# zhangting_v0_0.net
KiCad netlist of a schematic drawn in Altium Designer
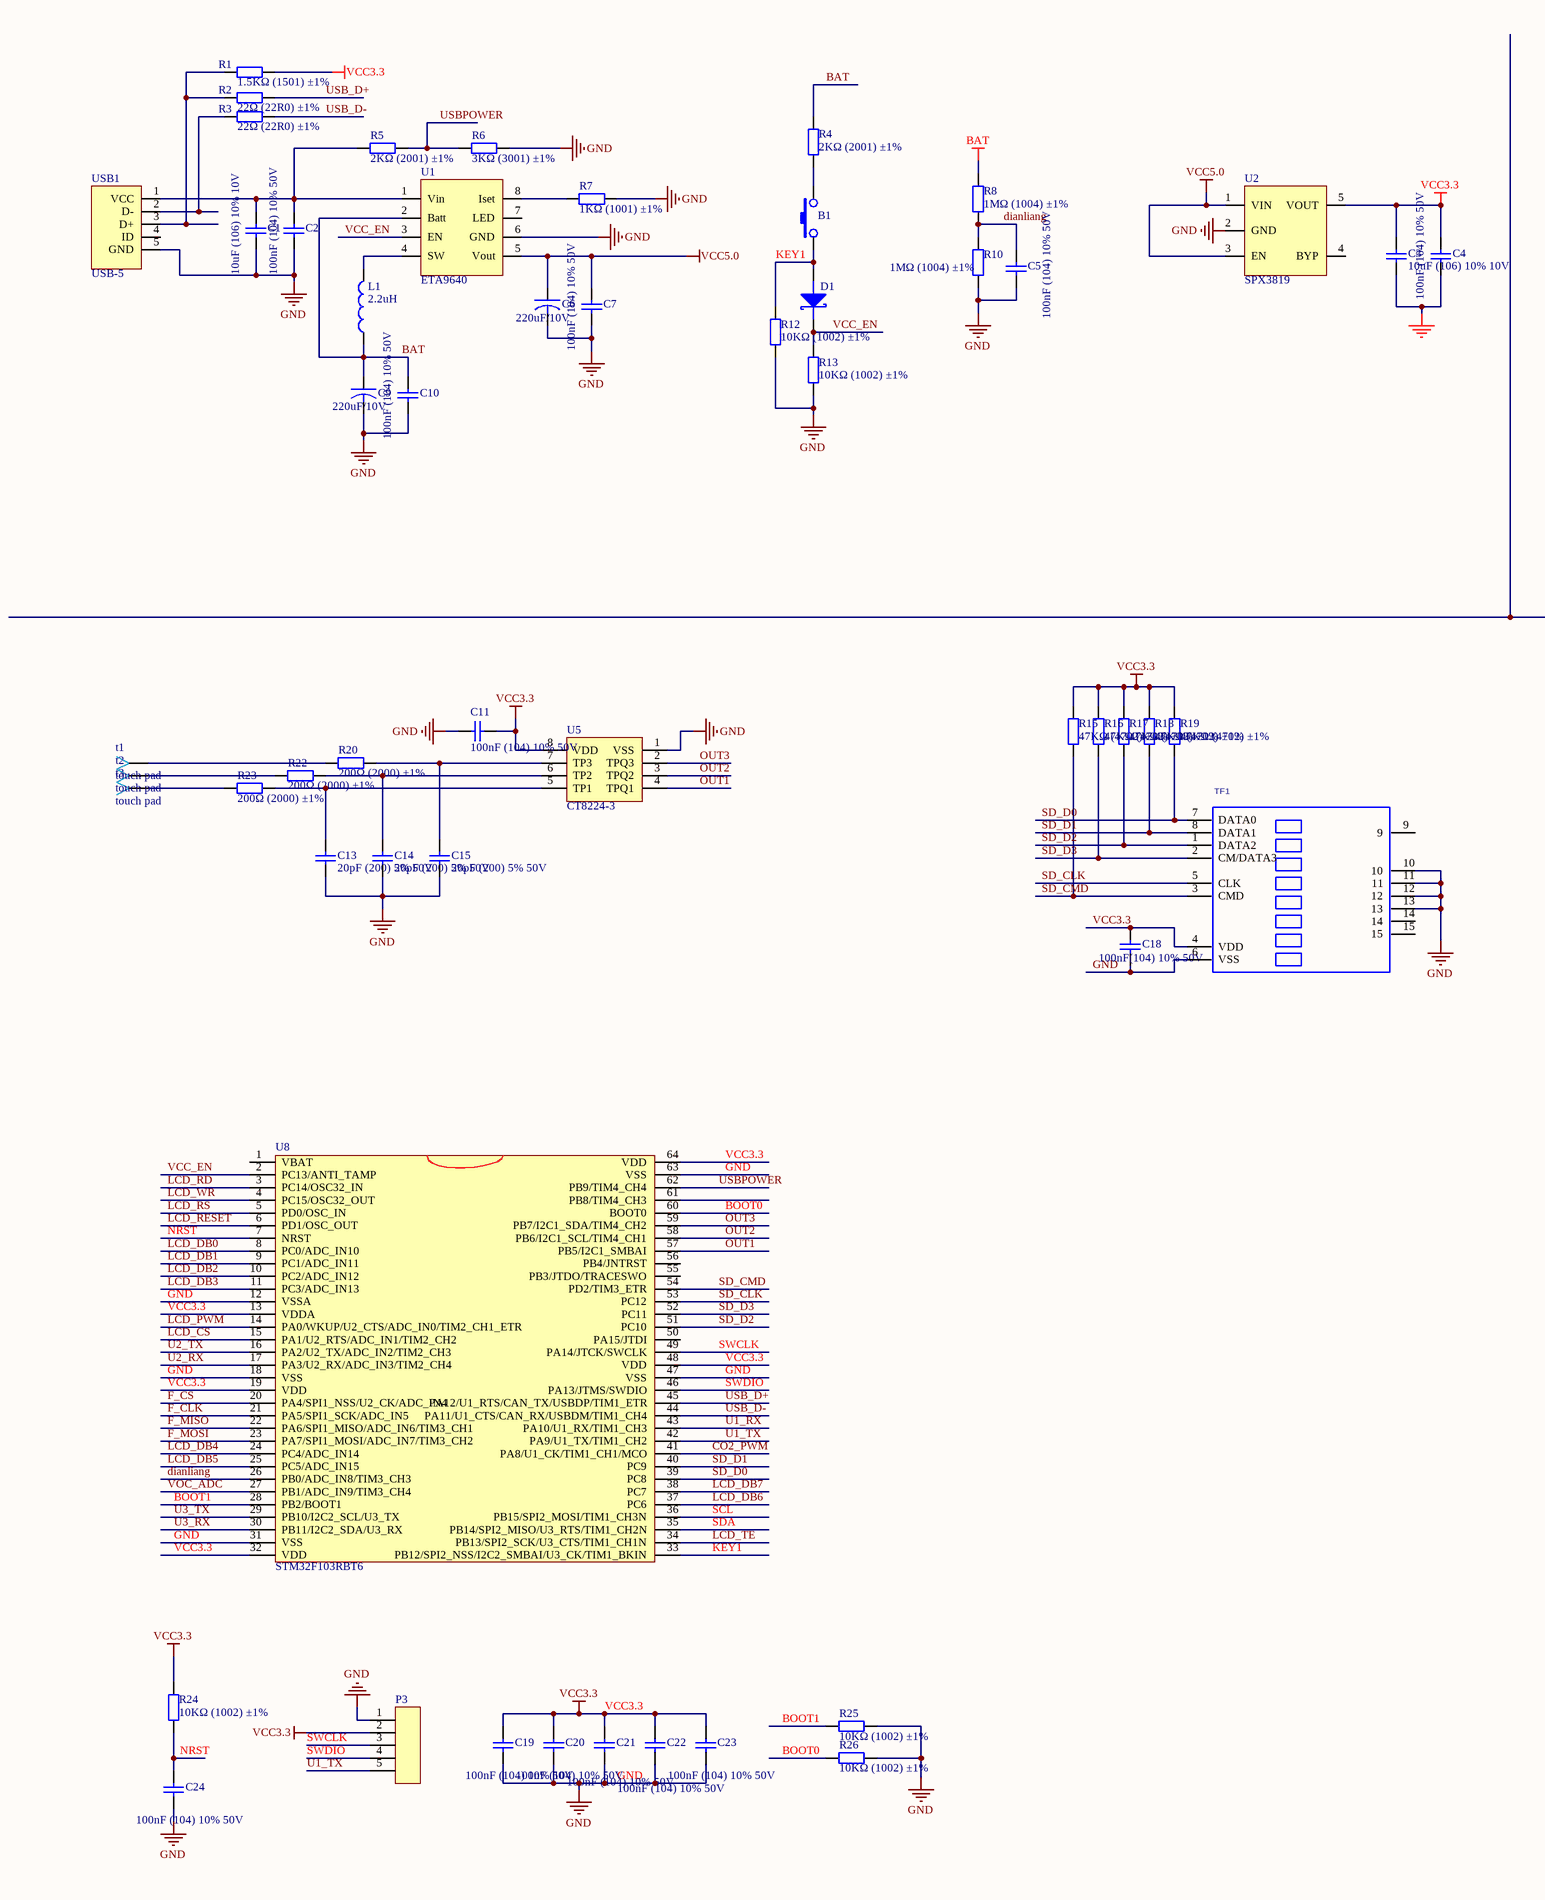
[diagram p0: zhangting v0.0.SchDoc, left]
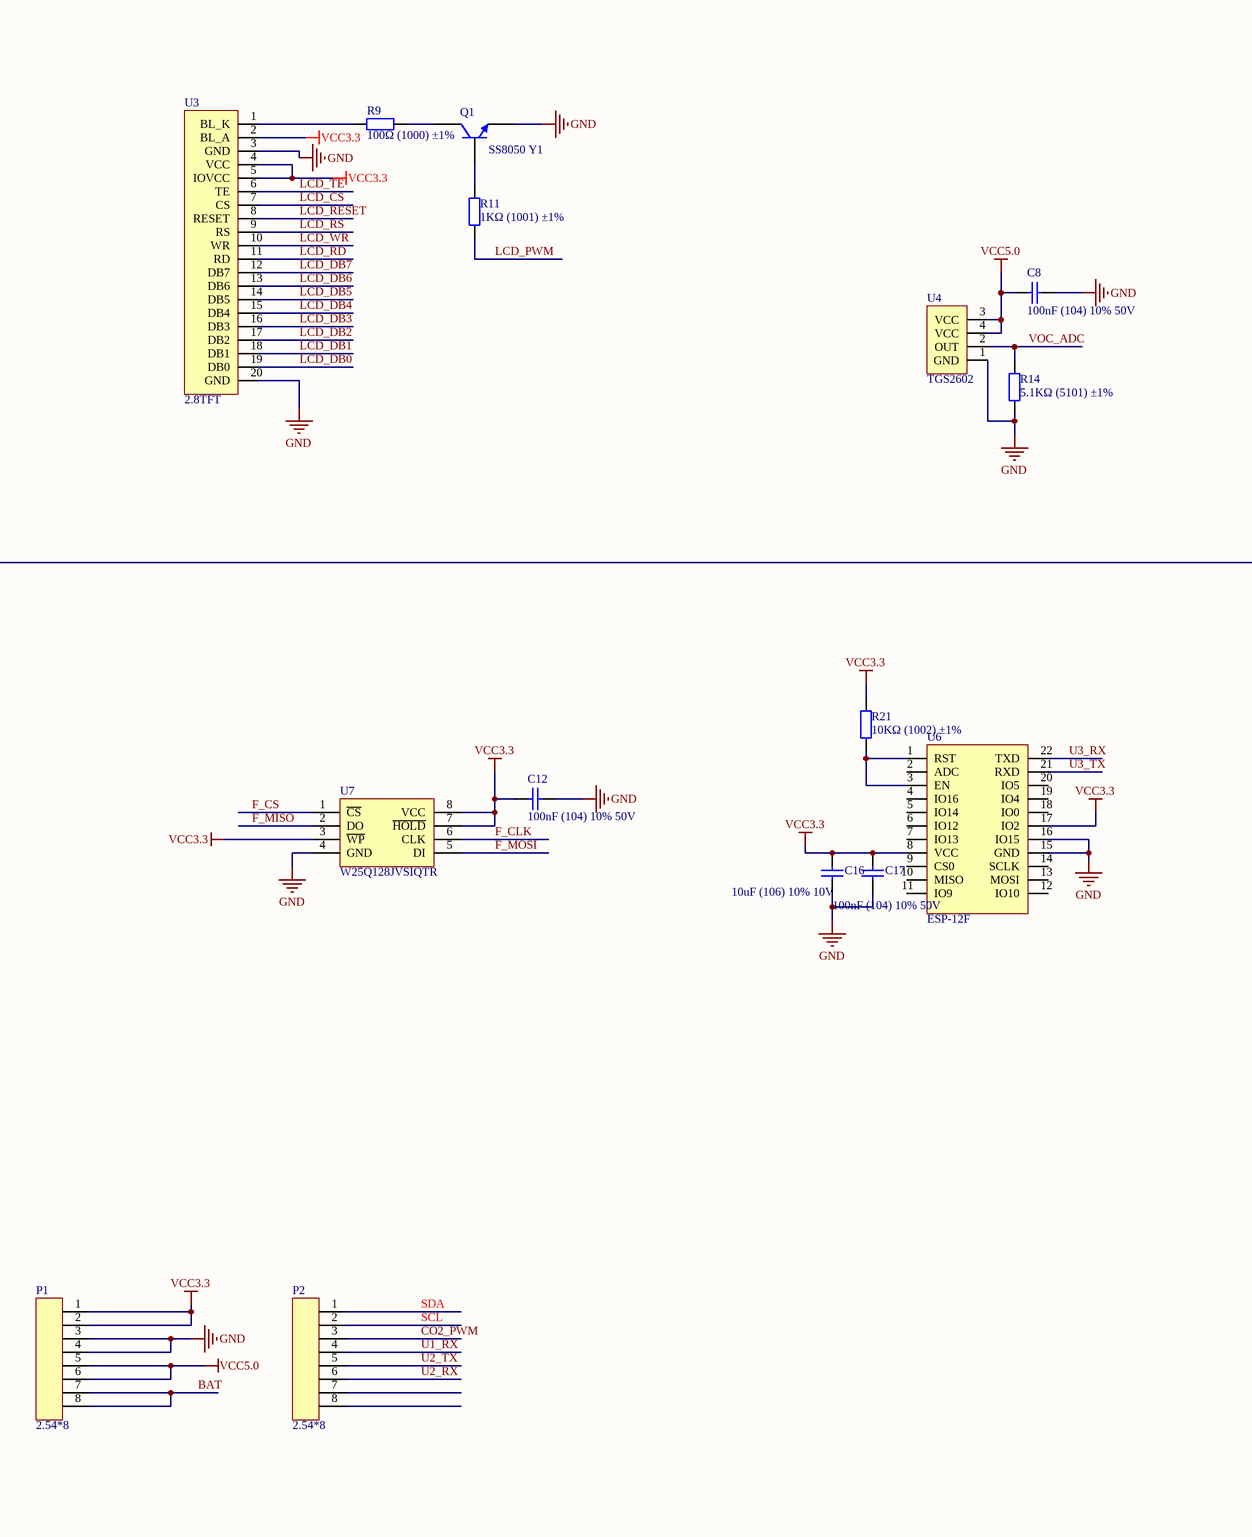
[diagram p1: zhangting v0.0.SchDoc, right]

(export (version "E")
  (design (tool "Eeschema 10.0.6"))
  (components
    (comp (ref "B1") (value "BUTTON侧贴") (footprint "BUTTON侧贴") (libsource (lib "分立器件") (part "BUTTON侧贴")))
    (comp (ref "C1")
      (value "10uF (106) 10% 10V")
      (footprint "0603_C")
      (description "贴片电容")
      (libsource (lib "Miscellaneous Devices LC") (part "0603 10uF (106) 10% 10V"))
    )
    (comp (ref "C2")
      (value "100nF (104) 10% 50V")
      (footprint "0603_C")
      (description "贴片电容")
      (libsource (lib "Miscellaneous Devices LC") (part "0603 100nF (104) 10% 50V"))
    )
    (comp (ref "C3")
      (value "10uF (106) 10% 10V")
      (footprint "0603_C")
      (description "贴片电容")
      (libsource (lib "Miscellaneous Devices LC") (part "0603 10uF (106) 10% 10V"))
    )
    (comp (ref "C4")
      (value "100nF (104) 10% 50V")
      (footprint "0603_C")
      (description "贴片电容")
      (libsource (lib "Miscellaneous Devices LC") (part "0603 100nF (104) 10% 50V"))
    )
    (comp (ref "C5")
      (value "100nF (104) 10% 50V")
      (footprint "0603_C")
      (description "贴片电容")
      (libsource (lib "Miscellaneous Devices LC") (part "0603 100nF (104) 10% 50V"))
    )
    (comp (ref "C6") (value "220uF/10V") (footprint "SMD-6.5mm") (libsource (lib "分立器件") (part "SMD-CAP")))
    (comp (ref "C7")
      (value "100nF (104) 10% 50V")
      (footprint "0603_C")
      (description "贴片电容")
      (libsource (lib "Miscellaneous Devices LC") (part "0603 100nF (104) 10% 50V"))
    )
    (comp (ref "C8")
      (value "100nF (104) 10% 50V")
      (footprint "0603_C")
      (description "贴片电容")
      (libsource (lib "Miscellaneous Devices LC") (part "0603 100nF (104) 10% 50V"))
    )
    (comp (ref "C9") (value "220uF/10V") (footprint "SMD-6.5mm") (libsource (lib "分立器件") (part "SMD-CAP")))
    (comp (ref "C10")
      (value "100nF (104) 10% 50V")
      (footprint "0603_C")
      (description "贴片电容")
      (libsource (lib "Miscellaneous Devices LC") (part "0603 100nF (104) 10% 50V"))
    )
    (comp (ref "C11")
      (value "100nF (104) 10% 50V")
      (footprint "0603_C")
      (description "贴片电容")
      (libsource (lib "Miscellaneous Devices LC") (part "0603 100nF (104) 10% 50V"))
    )
    (comp (ref "C12")
      (value "100nF (104) 10% 50V")
      (footprint "0603_C")
      (description "贴片电容")
      (libsource (lib "Miscellaneous Devices LC") (part "0603 100nF (104) 10% 50V"))
    )
    (comp (ref "C13")
      (value "20pF (200) 5% 50V")
      (footprint "0603_C")
      (description "贴片电容")
      (libsource (lib "Miscellaneous Devices LC") (part "0603 20pF (200) 5% 50V"))
    )
    (comp (ref "C14")
      (value "20pF (200) 5% 50V")
      (footprint "0603_C")
      (description "贴片电容")
      (libsource (lib "Miscellaneous Devices LC") (part "0603 20pF (200) 5% 50V"))
    )
    (comp (ref "C15")
      (value "20pF (200) 5% 50V")
      (footprint "0603_C")
      (description "贴片电容")
      (libsource (lib "Miscellaneous Devices LC") (part "0603 20pF (200) 5% 50V"))
    )
    (comp (ref "C16")
      (value "10uF (106) 10% 10V")
      (footprint "0603_C")
      (description "贴片电容")
      (libsource (lib "Miscellaneous Devices LC") (part "0603 10uF (106) 10% 10V"))
    )
    (comp (ref "C17")
      (value "100nF (104) 10% 50V")
      (footprint "0603_C")
      (description "贴片电容")
      (libsource (lib "Miscellaneous Devices LC") (part "0603 100nF (104) 10% 50V"))
    )
    (comp (ref "C18")
      (value "100nF(104) 10% 50V")
      (footprint "0805_C")
      (description "贴片电容")
      (libsource (lib "Miscellaneous Devices LC") (part "0805 100nF(104) 10% 50V"))
    )
    (comp (ref "C19")
      (value "100nF (104) 10% 50V")
      (footprint "0603_C")
      (description "贴片电容")
      (libsource (lib "Miscellaneous Devices LC") (part "0603 100nF (104) 10% 50V"))
    )
    (comp (ref "C20")
      (value "100nF (104) 10% 50V")
      (footprint "0603_C")
      (description "贴片电容")
      (libsource (lib "Miscellaneous Devices LC") (part "0603 100nF (104) 10% 50V"))
    )
    (comp (ref "C21")
      (value "100nF (104) 10% 50V")
      (footprint "0603_C")
      (description "贴片电容")
      (libsource (lib "Miscellaneous Devices LC") (part "0603 100nF (104) 10% 50V"))
    )
    (comp (ref "C22")
      (value "100nF (104) 10% 50V")
      (footprint "0603_C")
      (description "贴片电容")
      (libsource (lib "Miscellaneous Devices LC") (part "0603 100nF (104) 10% 50V"))
    )
    (comp (ref "C23")
      (value "100nF (104) 10% 50V")
      (footprint "0603_C")
      (description "贴片电容")
      (libsource (lib "Miscellaneous Devices LC") (part "0603 100nF (104) 10% 50V"))
    )
    (comp (ref "C24")
      (value "100nF (104) 10% 50V")
      (footprint "0603_C")
      (description "贴片电容")
      (libsource (lib "Miscellaneous Devices LC") (part "0603 100nF (104) 10% 50V"))
    )
    (comp (ref "D1") (value "IN4148") (footprint "DIODE(SMA)") (libsource (lib "分立器件") (part "肖特基二极管")))
    (comp (ref "L1") (value "2.2uH") (footprint "L(CD74)") (libsource (lib "分立器件") (part "L(CD74)")))
    (comp (ref "P1") (value "2.54*8") (footprint "2.54*8") (libsource (lib "接插件") (part "2.54*8")))
    (comp (ref "P2") (value "2.54*8") (footprint "2.54*8") (libsource (lib "接插件") (part "2.54*8")))
    (comp (ref "P3") (value "2.54*5") (footprint "2.54*5") (libsource (lib "接插件") (part "2.54*5")))
    (comp (ref "Q1")
      (value "SS8050 Y1")
      (footprint "SOT-23(SOT-23-3)")
      (description "三极管")
      (libsource (lib "Miscellaneous Devices LC") (part "SOT-23 SS8050 Y1"))
    )
    (comp (ref "R1")
      (value "1.5KΩ (1501) ±1%")
      (footprint "0603_R")
      (description "贴片电阻")
      (libsource (lib "Miscellaneous Devices LC") (part "0603 1.5KΩ (1501) 1%"))
    )
    (comp (ref "R2")
      (value "22Ω (22R0) ±1%")
      (footprint "0603_R")
      (description "贴片电阻")
      (libsource (lib "Miscellaneous Devices LC") (part "0603 22Ω (22R0) 1%"))
    )
    (comp (ref "R3")
      (value "22Ω (22R0) ±1%")
      (footprint "0603_R")
      (description "贴片电阻")
      (libsource (lib "Miscellaneous Devices LC") (part "0603 22Ω (22R0) 1%"))
    )
    (comp (ref "R4")
      (value "2KΩ (2001) ±1%")
      (footprint "0603_R")
      (description "贴片电阻")
      (libsource (lib "") (part "0603 2KΩ (2001) 1%_1"))
    )
    (comp (ref "R5")
      (value "2KΩ (2001) ±1%")
      (footprint "0603_R")
      (description "贴片电阻")
      (libsource (lib "Miscellaneous Devices LC") (part "0603 2KΩ (2001) 1%"))
    )
    (comp (ref "R6")
      (value "3KΩ (3001) ±1%")
      (footprint "0603_R")
      (description "贴片电阻")
      (libsource (lib "Miscellaneous Devices LC") (part "0603 3KΩ (3001) 1%"))
    )
    (comp (ref "R7")
      (value "1KΩ (1001) ±1%")
      (footprint "0603_R")
      (description "贴片电阻")
      (libsource (lib "") (part "0603 1KΩ (1001) 1%_1"))
    )
    (comp (ref "R8")
      (value "1MΩ (1004) ±1%")
      (footprint "0603_R")
      (description "贴片电阻")
      (libsource (lib "Miscellaneous Devices LC") (part "0603 1MΩ (1004) 1%"))
    )
    (comp (ref "R9")
      (value "100Ω (1000) ±1%")
      (footprint "0603_R")
      (description "贴片电阻")
      (libsource (lib "Miscellaneous Devices LC") (part "0603 100Ω (1000) 1%"))
    )
    (comp (ref "R10")
      (value "1MΩ (1004) ±1%")
      (footprint "0603_R")
      (description "贴片电阻")
      (libsource (lib "Miscellaneous Devices LC") (part "0603 1MΩ (1004) 1%"))
    )
    (comp (ref "R11")
      (value "1KΩ (1001) ±1%")
      (footprint "0603_R")
      (description "贴片电阻")
      (libsource (lib "Miscellaneous Devices LC") (part "0603 1KΩ (1001) 1%"))
    )
    (comp (ref "R12")
      (value "10KΩ (1002) ±1%")
      (footprint "0603_R")
      (description "贴片电阻")
      (libsource (lib "") (part "0603 10KΩ (1002) 1%_1"))
    )
    (comp (ref "R13")
      (value "10KΩ (1002) ±1%")
      (footprint "0603_R")
      (description "贴片电阻")
      (libsource (lib "") (part "0603 10KΩ (1002) 1%_1"))
    )
    (comp (ref "R14")
      (value "5.1KΩ (5101) ±1%")
      (footprint "0603_R")
      (description "贴片电阻")
      (libsource (lib "Miscellaneous Devices LC") (part "0603 5.1KΩ (5101) 1%"))
    )
    (comp (ref "R15")
      (value "47KΩ (4702) ±1%")
      (footprint "0603_R")
      (description "贴片电阻")
      (libsource (lib "Miscellaneous Devices LC") (part "0603 47KΩ (4702) 1%"))
    )
    (comp (ref "R16")
      (value "47KΩ (4702) ±1%")
      (footprint "0603_R")
      (description "贴片电阻")
      (libsource (lib "Miscellaneous Devices LC") (part "0603 47KΩ (4702) 1%"))
    )
    (comp (ref "R17")
      (value "47KΩ (4702) ±1%")
      (footprint "0603_R")
      (description "贴片电阻")
      (libsource (lib "Miscellaneous Devices LC") (part "0603 47KΩ (4702) 1%"))
    )
    (comp (ref "R18")
      (value "47KΩ (4702) ±1%")
      (footprint "0603_R")
      (description "贴片电阻")
      (libsource (lib "Miscellaneous Devices LC") (part "0603 47KΩ (4702) 1%"))
    )
    (comp (ref "R19")
      (value "47KΩ (4702) ±1%")
      (footprint "0603_R")
      (description "贴片电阻")
      (libsource (lib "Miscellaneous Devices LC") (part "0603 47KΩ (4702) 1%"))
    )
    (comp (ref "R20")
      (value "200Ω (2000) ±1%")
      (footprint "0603_R")
      (description "贴片电阻")
      (libsource (lib "Miscellaneous Devices LC") (part "0603 200Ω (2000) 1%"))
    )
    (comp (ref "R21")
      (value "10KΩ (1002) ±1%")
      (footprint "0603_R")
      (description "贴片电阻")
      (libsource (lib "") (part "0603 10KΩ (1002) 1%_1"))
    )
    (comp (ref "R22")
      (value "200Ω (2000) ±1%")
      (footprint "0603_R")
      (description "贴片电阻")
      (libsource (lib "Miscellaneous Devices LC") (part "0603 200Ω (2000) 1%"))
    )
    (comp (ref "R23")
      (value "200Ω (2000) ±1%")
      (footprint "0603_R")
      (description "贴片电阻")
      (libsource (lib "Miscellaneous Devices LC") (part "0603 200Ω (2000) 1%"))
    )
    (comp (ref "R24")
      (value "10KΩ (1002) ±1%")
      (footprint "0603_R")
      (description "贴片电阻")
      (libsource (lib "") (part "0603 10KΩ (1002) 1%_1"))
    )
    (comp (ref "R25")
      (value "10KΩ (1002) ±1%")
      (footprint "0603_R")
      (description "贴片电阻")
      (libsource (lib "Miscellaneous Devices LC") (part "0603 10KΩ (1002) 1%"))
    )
    (comp (ref "R26")
      (value "10KΩ (1002) ±1%")
      (footprint "0603_R")
      (description "贴片电阻")
      (libsource (lib "Miscellaneous Devices LC") (part "0603 10KΩ (1002) 1%"))
    )
    (comp (ref "t1") (value "touch pad") (footprint "touch pad") (libsource (lib "分立器件") (part "touch pad")))
    (comp (ref "t2") (value "touch pad") (footprint "touch pad") (libsource (lib "分立器件") (part "touch pad")))
    (comp (ref "t3") (value "touch pad") (footprint "touch pad") (libsource (lib "分立器件") (part "touch pad")))
    (comp (ref "TF1")
      (value "TF_CARD")
      (footprint "TF_CARD")
      (libsource (lib "INDIA  Power V0.0.4") (part "TF_CARD"))
    )
    (comp (ref "U1") (value "ETA9640") (footprint "SOP-8") (libsource (lib "集成块") (part "ETA9640")))
    (comp (ref "U2") (value "SPX3819") (footprint "SOT23-5") (libsource (lib "集成块") (part "SPX3819")))
    (comp (ref "U3") (value "2.8TFT") (footprint "2.8TFT") (libsource (lib "集成块") (part "2.8TFT")))
    (comp (ref "U4") (value "TGS2602") (footprint "TGS2602") (libsource (lib "集成块") (part "TGS2602")))
    (comp (ref "U5") (value "CT8224-3") (footprint "SOP-8") (libsource (lib "DC-005") (part "CT8224-3")))
    (comp (ref "U6") (value "ESP-12F") (footprint "ESP-12F") (libsource (lib "集成块") (part "ESP-12F")))
    (comp (ref "U7")
      (value "W25Q128JVSIQTR")
      (footprint "SOIC-8_208mil")
      (description "Flash ROM")
      (libsource (lib "Miscellaneous Devices LC") (part "W25Q128JVSIQTR_[C97521]"))
    )
    (comp (ref "U8")
      (value "STM32F103RBT6")
      (footprint "LQFP64")
      (libsource (lib "STM32") (part "STM32F103RBT6"))
    )
    (comp (ref "USB1") (value "USB-5") (footprint "USB-5") (libsource (lib "接插件") (part "USB-5")))
  )
  (nets
    (net (code "1") (name "/BOOT0") (class "Default")
      (node (ref "R26") (pin "2") (pinfunction "2_2") (pintype "passive"))
      (node (ref "U8") (pin "60") (pinfunction "BOOT0_60") (pintype "passive"))
    )
    (net (code "2") (name "/BOOT1") (class "Default")
      (node (ref "R25") (pin "2") (pinfunction "2_2") (pintype "passive"))
      (node (ref "U8") (pin "28") (pinfunction "PB2/BOOT1_28") (pintype "passive"))
    )
    (net (code "3") (name "/CO2_PWM") (class "Default")
      (node (ref "P2") (pin "3") (pintype "passive"))
      (node (ref "U8") (pin "41") (pinfunction "PA8/U1_CK/TIM1_CH1/MCO_41") (pintype "passive"))
    )
    (net (code "4") (name "/F_CLK") (class "Default")
      (node (ref "U7") (pin "6") (pinfunction "CLK_6") (pintype "passive"))
      (node (ref "U8") (pin "21") (pinfunction "PA5/SPI1_SCK/ADC_IN5_21") (pintype "passive"))
    )
    (net (code "5") (name "/F_CS") (class "Default")
      (node (ref "U7") (pin "1") (pinfunction "~{CS}_1") (pintype "passive"))
      (node (ref "U8") (pin "20") (pinfunction "PA4/SPI1_NSS/U2_CK/ADC_IN4_20") (pintype "passive"))
    )
    (net (code "6") (name "/F_MISO") (class "Default")
      (node (ref "U7") (pin "2") (pinfunction "DO_2") (pintype "passive"))
      (node (ref "U8") (pin "22") (pinfunction "PA6/SPI1_MISO/ADC_IN6/TIM3_CH1_22") (pintype "passive"))
    )
    (net (code "7") (name "/F_MOSI") (class "Default")
      (node (ref "U7") (pin "5") (pinfunction "DI_5") (pintype "passive"))
      (node (ref "U8") (pin "23") (pinfunction "PA7/SPI1_MOSI/ADC_IN7/TIM3_CH2_23") (pintype "passive"))
    )
    (net (code "8") (name "/KEY1") (class "Default")
      (node (ref "B1") (pin "1") (pinfunction "1_1") (pintype "passive"))
      (node (ref "D1") (pin "1") (pinfunction "A_1") (pintype "passive"))
      (node (ref "R12") (pin "2") (pinfunction "2_2") (pintype "passive"))
      (node (ref "U8") (pin "33") (pinfunction "PB12/SPI2_NSS/I2C2_SMBAI/U3_CK/TIM1_BKIN_33") (pintype "passive"))
    )
    (net (code "9") (name "/LCD_CS") (class "Default")
      (node (ref "U3") (pin "7") (pinfunction "CS_7") (pintype "passive"))
      (node (ref "U8") (pin "15") (pinfunction "PA1/U2_RTS/ADC_IN1/TIM2_CH2_15") (pintype "passive"))
    )
    (net (code "10") (name "/LCD_DB0") (class "Default")
      (node (ref "U3") (pin "19") (pinfunction "DB0_19") (pintype "passive"))
      (node (ref "U8") (pin "8") (pinfunction "PC0/ADC_IN10_8") (pintype "passive"))
    )
    (net (code "11") (name "/LCD_DB1") (class "Default")
      (node (ref "U3") (pin "18") (pinfunction "DB1_18") (pintype "passive"))
      (node (ref "U8") (pin "9") (pinfunction "PC1/ADC_IN11_9") (pintype "passive"))
    )
    (net (code "12") (name "/LCD_DB2") (class "Default")
      (node (ref "U3") (pin "17") (pinfunction "DB2_17") (pintype "passive"))
      (node (ref "U8") (pin "10") (pinfunction "PC2/ADC_IN12_10") (pintype "passive"))
    )
    (net (code "13") (name "/LCD_DB3") (class "Default")
      (node (ref "U3") (pin "16") (pinfunction "DB3_16") (pintype "passive"))
      (node (ref "U8") (pin "11") (pinfunction "PC3/ADC_IN13_11") (pintype "passive"))
    )
    (net (code "14") (name "/LCD_DB4") (class "Default")
      (node (ref "U3") (pin "15") (pinfunction "DB4_15") (pintype "passive"))
      (node (ref "U8") (pin "24") (pinfunction "PC4/ADC_IN14_24") (pintype "passive"))
    )
    (net (code "15") (name "/LCD_DB5") (class "Default")
      (node (ref "U3") (pin "14") (pinfunction "DB5_14") (pintype "passive"))
      (node (ref "U8") (pin "25") (pinfunction "PC5/ADC_IN15_25") (pintype "passive"))
    )
    (net (code "16") (name "/LCD_DB6") (class "Default")
      (node (ref "U3") (pin "13") (pinfunction "DB6_13") (pintype "passive"))
      (node (ref "U8") (pin "37") (pinfunction "PC6_37") (pintype "passive"))
    )
    (net (code "17") (name "/LCD_DB7") (class "Default")
      (node (ref "U3") (pin "12") (pinfunction "DB7_12") (pintype "passive"))
      (node (ref "U8") (pin "38") (pinfunction "PC7_38") (pintype "passive"))
    )
    (net (code "18") (name "/LCD_PWM") (class "Default")
      (node (ref "R11") (pin "1") (pinfunction "1_1") (pintype "passive"))
      (node (ref "U8") (pin "14") (pinfunction "PA0/WKUP/U2_CTS/ADC_IN0/TIM2_CH1_ETR_14") (pintype "passive"))
    )
    (net (code "19") (name "/LCD_RD") (class "Default")
      (node (ref "U3") (pin "11") (pinfunction "RD_11") (pintype "passive"))
      (node (ref "U8") (pin "3") (pinfunction "PC14/OSC32_IN_3") (pintype "passive"))
    )
    (net (code "20") (name "/LCD_RESET") (class "Default")
      (node (ref "U3") (pin "8") (pinfunction "RESET_8") (pintype "passive"))
      (node (ref "U8") (pin "6") (pinfunction "PD1/OSC_OUT_6") (pintype "passive"))
    )
    (net (code "21") (name "/LCD_RS") (class "Default")
      (node (ref "U3") (pin "9") (pinfunction "RS_9") (pintype "passive"))
      (node (ref "U8") (pin "5") (pinfunction "PD0/OSC_IN_5") (pintype "passive"))
    )
    (net (code "22") (name "/LCD_TE") (class "Default")
      (node (ref "U3") (pin "6") (pinfunction "TE_6") (pintype "passive"))
      (node (ref "U8") (pin "34") (pinfunction "PB13/SPI2_SCK/U3_CTS/TIM1_CH1N_34") (pintype "passive"))
    )
    (net (code "23") (name "/LCD_WR") (class "Default")
      (node (ref "U3") (pin "10") (pinfunction "WR_10") (pintype "passive"))
      (node (ref "U8") (pin "4") (pinfunction "PC15/OSC32_OUT_4") (pintype "passive"))
    )
    (net (code "24") (name "/NRST") (class "Default")
      (node (ref "C24") (pin "2") (pinfunction "2_2") (pintype "passive"))
      (node (ref "R24") (pin "1") (pinfunction "1_1") (pintype "passive"))
      (node (ref "U8") (pin "7") (pinfunction "NRST_7") (pintype "passive"))
    )
    (net (code "25") (name "/OUT1") (class "Default")
      (node (ref "U5") (pin "4") (pinfunction "TPQ1_4") (pintype "passive"))
      (node (ref "U8") (pin "57") (pinfunction "PB5/I2C1_SMBAI_57") (pintype "passive"))
    )
    (net (code "26") (name "/OUT2") (class "Default")
      (node (ref "U5") (pin "3") (pinfunction "TPQ2_3") (pintype "passive"))
      (node (ref "U8") (pin "58") (pinfunction "PB6/I2C1_SCL/TIM4_CH1_58") (pintype "passive"))
    )
    (net (code "27") (name "/OUT3") (class "Default")
      (node (ref "U5") (pin "2") (pinfunction "TPQ3_2") (pintype "passive"))
      (node (ref "U8") (pin "59") (pinfunction "PB7/I2C1_SDA/TIM4_CH2_59") (pintype "passive"))
    )
    (net (code "28") (name "/SCL") (class "Default")
      (node (ref "P2") (pin "2") (pintype "passive"))
      (node (ref "U8") (pin "36") (pinfunction "PB15/SPI2_MOSI/TIM1_CH3N_36") (pintype "passive"))
    )
    (net (code "29") (name "/SDA") (class "Default")
      (node (ref "P2") (pin "1") (pintype "passive"))
      (node (ref "U8") (pin "35") (pinfunction "PB14/SPI2_MISO/U3_RTS/TIM1_CH2N_35") (pintype "passive"))
    )
    (net (code "30") (name "/SD_CLK") (class "Default")
      (node (ref "TF1") (pin "5") (pinfunction "CLK_5") (pintype "passive"))
      (node (ref "U8") (pin "53") (pinfunction "PC12_53") (pintype "passive"))
    )
    (net (code "31") (name "/SD_CMD") (class "Default")
      (node (ref "R15") (pin "1") (pinfunction "1_1") (pintype "passive"))
      (node (ref "TF1") (pin "3") (pinfunction "CMD_3") (pintype "passive"))
      (node (ref "U8") (pin "54") (pinfunction "PD2/TIM3_ETR_54") (pintype "passive"))
    )
    (net (code "32") (name "/SD_D0") (class "Default")
      (node (ref "R19") (pin "1") (pinfunction "1_1") (pintype "passive"))
      (node (ref "TF1") (pin "7") (pinfunction "DATA0_7") (pintype "passive"))
      (node (ref "U8") (pin "39") (pinfunction "PC8_39") (pintype "passive"))
    )
    (net (code "33") (name "/SD_D1") (class "Default")
      (node (ref "R18") (pin "1") (pinfunction "1_1") (pintype "passive"))
      (node (ref "TF1") (pin "8") (pinfunction "DATA1_8") (pintype "passive"))
      (node (ref "U8") (pin "40") (pinfunction "PC9_40") (pintype "passive"))
    )
    (net (code "34") (name "/SD_D2") (class "Default")
      (node (ref "R17") (pin "1") (pinfunction "1_1") (pintype "passive"))
      (node (ref "TF1") (pin "1") (pinfunction "DATA2_1") (pintype "passive"))
      (node (ref "U8") (pin "51") (pinfunction "PC10_51") (pintype "passive"))
    )
    (net (code "35") (name "/SD_D3") (class "Default")
      (node (ref "R16") (pin "1") (pinfunction "1_1") (pintype "passive"))
      (node (ref "TF1") (pin "2") (pinfunction "CM/DATA3_2") (pintype "passive"))
      (node (ref "U8") (pin "52") (pinfunction "PC11_52") (pintype "passive"))
    )
    (net (code "36") (name "/SWCLK") (class "Default")
      (node (ref "P3") (pin "3") (pintype "passive"))
      (node (ref "U8") (pin "49") (pinfunction "PA14/JTCK/SWCLK_49") (pintype "passive"))
    )
    (net (code "37") (name "/SWDIO") (class "Default")
      (node (ref "P3") (pin "4") (pintype "passive"))
      (node (ref "U8") (pin "46") (pinfunction "PA13/JTMS/SWDIO_46") (pintype "passive"))
    )
    (net (code "38") (name "/U1_RX") (class "Default")
      (node (ref "P2") (pin "4") (pintype "passive"))
      (node (ref "U8") (pin "43") (pinfunction "PA10/U1_RX/TIM1_CH3_43") (pintype "passive"))
    )
    (net (code "39") (name "/U1_TX") (class "Default")
      (node (ref "P3") (pin "5") (pintype "passive"))
      (node (ref "U8") (pin "42") (pinfunction "PA9/U1_TX/TIM1_CH2_42") (pintype "passive"))
    )
    (net (code "40") (name "/U2_RX") (class "Default")
      (node (ref "P2") (pin "6") (pintype "passive"))
      (node (ref "U8") (pin "17") (pinfunction "PA3/U2_RX/ADC_IN3/TIM2_CH4_17") (pintype "passive"))
    )
    (net (code "41") (name "/U2_TX") (class "Default")
      (node (ref "P2") (pin "5") (pintype "passive"))
      (node (ref "U8") (pin "16") (pinfunction "PA2/U2_TX/ADC_IN2/TIM2_CH3_16") (pintype "passive"))
    )
    (net (code "42") (name "/U3_RX") (class "Default")
      (node (ref "U6") (pin "22") (pinfunction "TXD_22") (pintype "passive"))
      (node (ref "U8") (pin "30") (pinfunction "PB11/I2C2_SDA/U3_RX_30") (pintype "passive"))
    )
    (net (code "43") (name "/U3_TX") (class "Default")
      (node (ref "U6") (pin "21") (pinfunction "RXD_21") (pintype "passive"))
      (node (ref "U8") (pin "29") (pinfunction "PB10/I2C2_SCL/U3_TX_29") (pintype "passive"))
    )
    (net (code "44") (name "/USBPOWER") (class "Default")
      (node (ref "R5") (pin "1") (pinfunction "1_1") (pintype "passive"))
      (node (ref "R6") (pin "1") (pinfunction "1_1") (pintype "passive"))
      (node (ref "U8") (pin "62") (pinfunction "PB9/TIM4_CH4_62") (pintype "passive"))
    )
    (net (code "45") (name "/USB_D+") (class "Default")
      (node (ref "R2") (pin "2") (pinfunction "2_2") (pintype "passive"))
      (node (ref "U8") (pin "45") (pinfunction "PA12/U1_RTS/CAN_TX/USBDP/TIM1_ETR_45") (pintype "passive"))
    )
    (net (code "46") (name "/USB_D-") (class "Default")
      (node (ref "R3") (pin "2") (pinfunction "2_2") (pintype "passive"))
      (node (ref "U8") (pin "44") (pinfunction "PA11/U1_CTS/CAN_RX/USBDM/TIM1_CH4_44") (pintype "passive"))
    )
    (net (code "47") (name "/VCC_EN") (class "Default")
      (node (ref "D1") (pin "2") (pinfunction "K_2") (pintype "passive"))
      (node (ref "R13") (pin "2") (pinfunction "2_2") (pintype "passive"))
      (node (ref "U1") (pin "3") (pinfunction "EN_3") (pintype "passive"))
      (node (ref "U8") (pin "2") (pinfunction "PC13/ANTI_TAMP_2") (pintype "passive"))
    )
    (net (code "48") (name "/VOC_ADC") (class "Default")
      (node (ref "R14") (pin "2") (pinfunction "2_2") (pintype "passive"))
      (node (ref "U4") (pin "2") (pinfunction "OUT_2") (pintype "passive"))
      (node (ref "U8") (pin "27") (pinfunction "PB1/ADC_IN9/TIM3_CH4_27") (pintype "passive"))
    )
    (net (code "49") (name "/dianliang") (class "Default")
      (node (ref "C5") (pin "2") (pinfunction "2_2") (pintype "passive"))
      (node (ref "R10") (pin "2") (pinfunction "2_2") (pintype "passive"))
      (node (ref "R8") (pin "1") (pinfunction "1_1") (pintype "passive"))
      (node (ref "U8") (pin "26") (pinfunction "PB0/ADC_IN8/TIM3_CH3_26") (pintype "passive"))
    )
    (net (code "50") (name "BAT") (class "Default")
      (node (ref "C10") (pin "2") (pinfunction "2_2") (pintype "passive"))
      (node (ref "C9") (pin "1") (pinfunction "1_1") (pintype "passive"))
      (node (ref "L1") (pin "1") (pinfunction "1_1") (pintype "passive"))
      (node (ref "P1") (pin "7") (pintype "passive"))
      (node (ref "P1") (pin "8") (pinfunction "8_8") (pintype "passive"))
      (node (ref "R4") (pin "2") (pinfunction "2_2") (pintype "passive"))
      (node (ref "R8") (pin "2") (pinfunction "2_2") (pintype "passive"))
      (node (ref "U1") (pin "2") (pinfunction "Batt_2") (pintype "passive"))
    )
    (net (code "51") (name "GND") (class "Default")
      (node (ref "C1") (pin "1") (pinfunction "1_1") (pintype "passive"))
      (node (ref "C10") (pin "1") (pinfunction "1_1") (pintype "passive"))
      (node (ref "C11") (pin "2") (pinfunction "2_2") (pintype "passive"))
      (node (ref "C12") (pin "1") (pinfunction "1_1") (pintype "passive"))
      (node (ref "C13") (pin "1") (pinfunction "1_1") (pintype "passive"))
      (node (ref "C14") (pin "1") (pinfunction "1_1") (pintype "passive"))
      (node (ref "C15") (pin "1") (pinfunction "1_1") (pintype "passive"))
      (node (ref "C16") (pin "1") (pinfunction "1_1") (pintype "passive"))
      (node (ref "C17") (pin "1") (pinfunction "1_1") (pintype "passive"))
      (node (ref "C18") (pin "1") (pinfunction "1_1") (pintype "passive"))
      (node (ref "C19") (pin "1") (pinfunction "1_1") (pintype "passive"))
      (node (ref "C2") (pin "1") (pinfunction "1_1") (pintype "passive"))
      (node (ref "C20") (pin "1") (pinfunction "1_1") (pintype "passive"))
      (node (ref "C21") (pin "1") (pinfunction "1_1") (pintype "passive"))
      (node (ref "C22") (pin "1") (pinfunction "1_1") (pintype "passive"))
      (node (ref "C23") (pin "1") (pinfunction "1_1") (pintype "passive"))
      (node (ref "C24") (pin "1") (pinfunction "1_1") (pintype "passive"))
      (node (ref "C3") (pin "1") (pinfunction "1_1") (pintype "passive"))
      (node (ref "C4") (pin "1") (pinfunction "1_1") (pintype "passive"))
      (node (ref "C5") (pin "1") (pinfunction "1_1") (pintype "passive"))
      (node (ref "C6") (pin "2") (pinfunction "2_2") (pintype "passive"))
      (node (ref "C7") (pin "1") (pinfunction "1_1") (pintype "passive"))
      (node (ref "C8") (pin "1") (pinfunction "1_1") (pintype "passive"))
      (node (ref "C9") (pin "2") (pinfunction "2_2") (pintype "passive"))
      (node (ref "P1") (pin "3") (pintype "passive"))
      (node (ref "P1") (pin "4") (pintype "passive"))
      (node (ref "P3") (pin "1") (pintype "passive"))
      (node (ref "Q1") (pin "2") (pinfunction "E_2") (pintype "passive"))
      (node (ref "R10") (pin "1") (pinfunction "1_1") (pintype "passive"))
      (node (ref "R12") (pin "1") (pinfunction "1_1") (pintype "passive"))
      (node (ref "R13") (pin "1") (pinfunction "1_1") (pintype "passive"))
      (node (ref "R14") (pin "1") (pinfunction "1_1") (pintype "passive"))
      (node (ref "R25") (pin "1") (pinfunction "1_1") (pintype "passive"))
      (node (ref "R26") (pin "1") (pinfunction "1_1") (pintype "passive"))
      (node (ref "R6") (pin "2") (pinfunction "2_2") (pintype "passive"))
      (node (ref "R7") (pin "2") (pinfunction "2_2") (pintype "passive"))
      (node (ref "TF1") (pin "10") (pinfunction "10_10") (pintype "passive"))
      (node (ref "TF1") (pin "11") (pinfunction "11_11") (pintype "passive"))
      (node (ref "TF1") (pin "12") (pinfunction "12_12") (pintype "passive"))
      (node (ref "TF1") (pin "13") (pinfunction "13_13") (pintype "passive"))
      (node (ref "TF1") (pin "6") (pinfunction "VSS_6") (pintype "passive"))
      (node (ref "U1") (pin "6") (pinfunction "GND_6") (pintype "passive"))
      (node (ref "U2") (pin "2") (pinfunction "GND_2") (pintype "passive"))
      (node (ref "U3") (pin "20") (pinfunction "GND_20") (pintype "passive"))
      (node (ref "U3") (pin "3") (pinfunction "GND_3") (pintype "passive"))
      (node (ref "U4") (pin "1") (pinfunction "GND_1") (pintype "passive"))
      (node (ref "U5") (pin "1") (pinfunction "VSS_1") (pintype "passive"))
      (node (ref "U6") (pin "15") (pinfunction "GND_15") (pintype "passive"))
      (node (ref "U6") (pin "16") (pinfunction "IO15_16") (pintype "passive"))
      (node (ref "U7") (pin "4") (pinfunction "GND_4") (pintype "passive"))
      (node (ref "U8") (pin "12") (pinfunction "VSSA_12") (pintype "passive"))
      (node (ref "U8") (pin "18") (pinfunction "VSS_18") (pintype "passive"))
      (node (ref "U8") (pin "31") (pinfunction "VSS_31") (pintype "passive"))
      (node (ref "U8") (pin "47") (pinfunction "VSS_47") (pintype "passive"))
      (node (ref "U8") (pin "63") (pinfunction "VSS_63") (pintype "passive"))
      (node (ref "USB1") (pin "5") (pinfunction "GND_5") (pintype "passive"))
    )
    (net (code "52") (name "Net-(B1-Pad2)") (class "Default")
      (node (ref "B1") (pin "2") (pinfunction "2_2") (pintype "passive"))
      (node (ref "R4") (pin "1") (pinfunction "1_1") (pintype "passive"))
    )
    (net (code "53") (name "Net-(Q1-B)") (class "Default")
      (node (ref "Q1") (pin "1") (pinfunction "B_1") (pintype "passive"))
      (node (ref "R11") (pin "2") (pinfunction "2_2") (pintype "passive"))
    )
    (net (code "54") (name "Net-(Q1-C)") (class "Default")
      (node (ref "Q1") (pin "3") (pinfunction "C_3") (pintype "passive"))
      (node (ref "R9") (pin "2") (pinfunction "2_2") (pintype "passive"))
    )
    (net (code "55") (name "Net-(R20-Pad1)") (class "Default")
      (node (ref "R20") (pin "1") (pinfunction "1_1") (pintype "passive"))
      (node (ref "t1") (pin "1") (pinfunction "1_1") (pintype "passive"))
    )
    (net (code "56") (name "Net-(R22-Pad1)") (class "Default")
      (node (ref "R22") (pin "1") (pinfunction "1_1") (pintype "passive"))
      (node (ref "t2") (pin "1") (pinfunction "1_1") (pintype "passive"))
    )
    (net (code "57") (name "Net-(R23-Pad1)") (class "Default")
      (node (ref "R23") (pin "1") (pinfunction "1_1") (pintype "passive"))
      (node (ref "t3") (pin "1") (pinfunction "1_1") (pintype "passive"))
    )
    (net (code "58") (name "Net-(U1-Iset)") (class "Default")
      (node (ref "R7") (pin "1") (pinfunction "1_1") (pintype "passive"))
      (node (ref "U1") (pin "8") (pinfunction "Iset_8") (pintype "passive"))
    )
    (net (code "59") (name "Net-(U1-SW)") (class "Default")
      (node (ref "L1") (pin "2") (pinfunction "2_2") (pintype "passive"))
      (node (ref "U1") (pin "4") (pinfunction "SW_4") (pintype "passive"))
    )
    (net (code "60") (name "Net-(U1-Vin)") (class "Default")
      (node (ref "C1") (pin "2") (pinfunction "2_2") (pintype "passive"))
      (node (ref "C2") (pin "2") (pinfunction "2_2") (pintype "passive"))
      (node (ref "R5") (pin "2") (pinfunction "2_2") (pintype "passive"))
      (node (ref "U1") (pin "1") (pinfunction "Vin_1") (pintype "passive"))
      (node (ref "USB1") (pin "1") (pinfunction "VCC_1") (pintype "passive"))
    )
    (net (code "61") (name "Net-(U3-BL_K)") (class "Default")
      (node (ref "R9") (pin "1") (pinfunction "1_1") (pintype "passive"))
      (node (ref "U3") (pin "1") (pinfunction "BL_K_1") (pintype "passive"))
    )
    (net (code "62") (name "Net-(U5-TP1)") (class "Default")
      (node (ref "C13") (pin "2") (pinfunction "2_2") (pintype "passive"))
      (node (ref "R23") (pin "2") (pinfunction "2_2") (pintype "passive"))
      (node (ref "U5") (pin "5") (pinfunction "TP1_5") (pintype "passive"))
    )
    (net (code "63") (name "Net-(U5-TP2)") (class "Default")
      (node (ref "C14") (pin "2") (pinfunction "2_2") (pintype "passive"))
      (node (ref "R22") (pin "2") (pinfunction "2_2") (pintype "passive"))
      (node (ref "U5") (pin "6") (pinfunction "TP2_6") (pintype "passive"))
    )
    (net (code "64") (name "Net-(U5-TP3)") (class "Default")
      (node (ref "C15") (pin "2") (pinfunction "2_2") (pintype "passive"))
      (node (ref "R20") (pin "2") (pinfunction "2_2") (pintype "passive"))
      (node (ref "U5") (pin "7") (pinfunction "TP3_7") (pintype "passive"))
    )
    (net (code "65") (name "Net-(U6-EN)") (class "Default")
      (node (ref "R21") (pin "1") (pinfunction "1_1") (pintype "passive"))
      (node (ref "U6") (pin "1") (pinfunction "RST_1") (pintype "passive"))
      (node (ref "U6") (pin "3") (pinfunction "EN_3") (pintype "passive"))
    )
    (net (code "66") (name "Net-(USB1-D+)") (class "Default")
      (node (ref "R1") (pin "1") (pinfunction "1_1") (pintype "passive"))
      (node (ref "R2") (pin "1") (pinfunction "1_1") (pintype "passive"))
      (node (ref "USB1") (pin "3") (pinfunction "D+_3") (pintype "passive"))
    )
    (net (code "67") (name "Net-(USB1-D-)") (class "Default")
      (node (ref "R3") (pin "1") (pinfunction "1_1") (pintype "passive"))
      (node (ref "USB1") (pin "2") (pinfunction "D-_2") (pintype "passive"))
    )
    (net (code "68") (name "VCC3.3") (class "Default")
      (node (ref "C11") (pin "1") (pinfunction "1_1") (pintype "passive"))
      (node (ref "C12") (pin "2") (pinfunction "2_2") (pintype "passive"))
      (node (ref "C16") (pin "2") (pinfunction "2_2") (pintype "passive"))
      (node (ref "C17") (pin "2") (pinfunction "2_2") (pintype "passive"))
      (node (ref "C18") (pin "2") (pinfunction "2_2") (pintype "passive"))
      (node (ref "C19") (pin "2") (pinfunction "2_2") (pintype "passive"))
      (node (ref "C20") (pin "2") (pinfunction "2_2") (pintype "passive"))
      (node (ref "C21") (pin "2") (pinfunction "2_2") (pintype "passive"))
      (node (ref "C22") (pin "2") (pinfunction "2_2") (pintype "passive"))
      (node (ref "C23") (pin "2") (pinfunction "2_2") (pintype "passive"))
      (node (ref "C3") (pin "2") (pinfunction "2_2") (pintype "passive"))
      (node (ref "C4") (pin "2") (pinfunction "2_2") (pintype "passive"))
      (node (ref "P1") (pin "1") (pintype "passive"))
      (node (ref "P1") (pin "2") (pintype "passive"))
      (node (ref "P3") (pin "2") (pintype "passive"))
      (node (ref "R1") (pin "2") (pinfunction "2_2") (pintype "passive"))
      (node (ref "R15") (pin "2") (pinfunction "2_2") (pintype "passive"))
      (node (ref "R16") (pin "2") (pinfunction "2_2") (pintype "passive"))
      (node (ref "R17") (pin "2") (pinfunction "2_2") (pintype "passive"))
      (node (ref "R18") (pin "2") (pinfunction "2_2") (pintype "passive"))
      (node (ref "R19") (pin "2") (pinfunction "2_2") (pintype "passive"))
      (node (ref "R21") (pin "2") (pinfunction "2_2") (pintype "passive"))
      (node (ref "R24") (pin "2") (pinfunction "2_2") (pintype "passive"))
      (node (ref "TF1") (pin "4") (pinfunction "VDD_4") (pintype "passive"))
      (node (ref "U2") (pin "5") (pinfunction "VOUT_5") (pintype "passive"))
      (node (ref "U3") (pin "2") (pinfunction "BL_A_2") (pintype "passive"))
      (node (ref "U3") (pin "4") (pinfunction "VCC_4") (pintype "passive"))
      (node (ref "U3") (pin "5") (pinfunction "IOVCC_5") (pintype "passive"))
      (node (ref "U5") (pin "8") (pinfunction "VDD_8") (pintype "passive"))
      (node (ref "U6") (pin "17") (pinfunction "IO2_17") (pintype "passive"))
      (node (ref "U6") (pin "8") (pinfunction "VCC_8") (pintype "passive"))
      (node (ref "U7") (pin "3") (pinfunction "~{WP}_3") (pintype "passive"))
      (node (ref "U7") (pin "7") (pinfunction "~{HOLD}_7") (pintype "passive"))
      (node (ref "U7") (pin "8") (pinfunction "VCC_8") (pintype "passive"))
      (node (ref "U8") (pin "13") (pinfunction "VDDA_13") (pintype "passive"))
      (node (ref "U8") (pin "19") (pinfunction "VDD_19") (pintype "passive"))
      (node (ref "U8") (pin "32") (pinfunction "VDD_32") (pintype "passive"))
      (node (ref "U8") (pin "48") (pinfunction "VDD_48") (pintype "passive"))
      (node (ref "U8") (pin "64") (pinfunction "VDD_64") (pintype "passive"))
    )
    (net (code "69") (name "VCC5.0") (class "Default")
      (node (ref "C6") (pin "1") (pinfunction "1_1") (pintype "passive"))
      (node (ref "C7") (pin "2") (pinfunction "2_2") (pintype "passive"))
      (node (ref "C8") (pin "2") (pinfunction "2_2") (pintype "passive"))
      (node (ref "P1") (pin "5") (pintype "passive"))
      (node (ref "P1") (pin "6") (pintype "passive"))
      (node (ref "U1") (pin "5") (pinfunction "Vout_5") (pintype "passive"))
      (node (ref "U2") (pin "1") (pinfunction "VIN_1") (pintype "passive"))
      (node (ref "U2") (pin "3") (pinfunction "EN_3") (pintype "passive"))
      (node (ref "U4") (pin "3") (pinfunction "VCC_3") (pintype "passive"))
      (node (ref "U4") (pin "4") (pinfunction "VCC_4") (pintype "passive"))
    )
    (net (code "70") (name "unconnected-(P2-Pad7)") (class "Default")
      (node (ref "P2") (pin "7") (pintype "passive"))
    )
    (net (code "71") (name "unconnected-(P2-Pad8)") (class "Default")
      (node (ref "P2") (pin "8") (pinfunction "8_8") (pintype "passive"))
    )
    (net (code "72") (name "unconnected-(TF1-Pad9)") (class "Default")
      (node (ref "TF1") (pin "9") (pinfunction "9_9") (pintype "passive"))
    )
    (net (code "73") (name "unconnected-(TF1-Pad14)") (class "Default")
      (node (ref "TF1") (pin "14") (pinfunction "14_14") (pintype "passive"))
    )
    (net (code "74") (name "unconnected-(TF1-Pad15)") (class "Default")
      (node (ref "TF1") (pin "15") (pinfunction "15_15") (pintype "passive"))
    )
    (net (code "75") (name "unconnected-(U1-LED-Pad7)") (class "Default")
      (node (ref "U1") (pin "7") (pinfunction "LED_7") (pintype "passive"))
    )
    (net (code "76") (name "unconnected-(U2-BYP-Pad4)") (class "Default")
      (node (ref "U2") (pin "4") (pinfunction "BYP_4") (pintype "passive"))
    )
    (net (code "77") (name "unconnected-(U6-ADC-Pad2)") (class "Default")
      (node (ref "U6") (pin "2") (pinfunction "ADC_2") (pintype "passive"))
    )
    (net (code "78") (name "unconnected-(U6-CS0-Pad9)") (class "Default")
      (node (ref "U6") (pin "9") (pinfunction "CS0_9") (pintype "passive"))
    )
    (net (code "79") (name "unconnected-(U6-IO0-Pad18)") (class "Default")
      (node (ref "U6") (pin "18") (pinfunction "IO0_18") (pintype "passive"))
    )
    (net (code "80") (name "unconnected-(U6-IO4-Pad19)") (class "Default")
      (node (ref "U6") (pin "19") (pinfunction "IO4_19") (pintype "passive"))
    )
    (net (code "81") (name "unconnected-(U6-IO5-Pad20)") (class "Default")
      (node (ref "U6") (pin "20") (pinfunction "IO5_20") (pintype "passive"))
    )
    (net (code "82") (name "unconnected-(U6-IO9-Pad11)") (class "Default")
      (node (ref "U6") (pin "11") (pinfunction "IO9_11") (pintype "passive"))
    )
    (net (code "83") (name "unconnected-(U6-IO10-Pad12)") (class "Default")
      (node (ref "U6") (pin "12") (pinfunction "IO10_12") (pintype "passive"))
    )
    (net (code "84") (name "unconnected-(U6-IO12-Pad6)") (class "Default")
      (node (ref "U6") (pin "6") (pinfunction "IO12_6") (pintype "passive"))
    )
    (net (code "85") (name "unconnected-(U6-IO13-Pad7)") (class "Default")
      (node (ref "U6") (pin "7") (pinfunction "IO13_7") (pintype "passive"))
    )
    (net (code "86") (name "unconnected-(U6-IO14-Pad5)") (class "Default")
      (node (ref "U6") (pin "5") (pinfunction "IO14_5") (pintype "passive"))
    )
    (net (code "87") (name "unconnected-(U6-IO16-Pad4)") (class "Default")
      (node (ref "U6") (pin "4") (pinfunction "IO16_4") (pintype "passive"))
    )
    (net (code "88") (name "unconnected-(U6-MISO-Pad10)") (class "Default")
      (node (ref "U6") (pin "10") (pinfunction "MISO_10") (pintype "passive"))
    )
    (net (code "89") (name "unconnected-(U6-MOSI-Pad13)") (class "Default")
      (node (ref "U6") (pin "13") (pinfunction "MOSI_13") (pintype "passive"))
    )
    (net (code "90") (name "unconnected-(U6-SCLK-Pad14)") (class "Default")
      (node (ref "U6") (pin "14") (pinfunction "SCLK_14") (pintype "passive"))
    )
    (net (code "91") (name "unconnected-(U8-PA15{slash}JTDI-Pad50)") (class "Default")
      (node (ref "U8") (pin "50") (pinfunction "PA15/JTDI_50") (pintype "passive"))
    )
    (net (code "92") (name "unconnected-(U8-PB3{slash}JTDO{slash}TRACESWO-Pad55)") (class "Default")
      (node (ref "U8") (pin "55") (pinfunction "PB3/JTDO/TRACESWO_55") (pintype "passive"))
    )
    (net (code "93") (name "unconnected-(U8-PB4{slash}JNTRST-Pad56)") (class "Default")
      (node (ref "U8") (pin "56") (pinfunction "PB4/JNTRST_56") (pintype "passive"))
    )
    (net (code "94") (name "unconnected-(U8-PB8{slash}TIM4_CH3-Pad61)") (class "Default")
      (node (ref "U8") (pin "61") (pinfunction "PB8/TIM4_CH3_61") (pintype "passive"))
    )
    (net (code "95") (name "unconnected-(U8-VBAT-Pad1)") (class "Default")
      (node (ref "U8") (pin "1") (pinfunction "VBAT_1") (pintype "passive"))
    )
    (net (code "96") (name "unconnected-(USB1-ID-Pad4)") (class "Default")
      (node (ref "USB1") (pin "4") (pinfunction "ID_4") (pintype "passive"))
    )
  )
)
